# Sheet1.net
KiCad netlist of a schematic drawn in Altium Designer
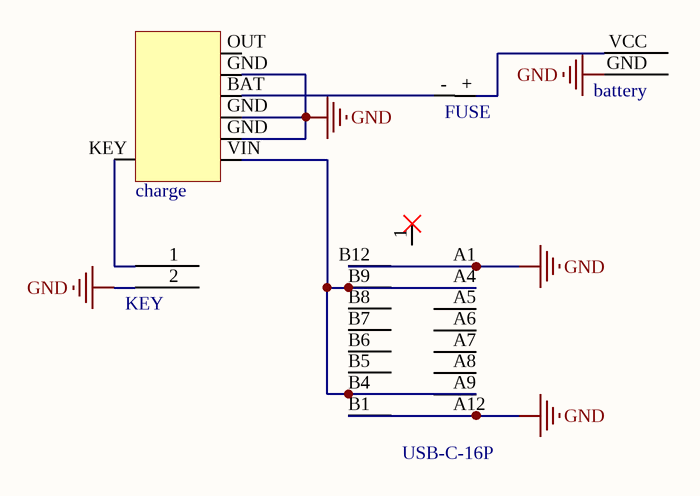
[diagram p0: Sheet1.SchDoc]

(export (version "E")
  (design (tool "Eeschema 10.0.6"))
  (components
    (comp (ref "battery")
      (value "battery")
      (footprint "battery")
      (libsource (lib "Schlib1") (part "battery"))
    )
    (comp (ref "charge") (value "charge") (footprint "charge") (libsource (lib "Schlib1") (part "charge")))
    (comp (ref "FUSE") (value "FUSE") (footprint "fuse") (libsource (lib "Schlib1") (part "FUSE")))
    (comp (ref "KEY") (value "KEY") (footprint "KEY") (libsource (lib "Schlib1") (part "KEY")))
    (comp (ref "USB-C")
      (value "USB-C-16P")
      (footprint "USB-C")
      (libsource (lib "Schlib1") (part "USB-C-16P"))
    )
  )
  (nets
    (net (code "1") (name "GND") (class "Default")
      (node (ref "KEY") (pin "2") (pinfunction "2_2") (pintype "passive"))
      (node (ref "USB-C") (pin "A1") (pinfunction "A1_A1") (pintype "passive"))
      (node (ref "USB-C") (pin "A12") (pinfunction "A12_A12") (pintype "passive"))
      (node (ref "USB-C") (pin "B1") (pinfunction "B1_B1") (pintype "passive"))
      (node (ref "USB-C") (pin "B12") (pinfunction "B12_B12") (pintype "passive"))
      (node (ref "battery") (pin "GND") (pinfunction "GND_GND") (pintype "passive"))
      (node (ref "charge") (pin "GND") (pinfunction "GND_GND") (pintype "passive"))
    )
    (net (code "2") (name "Net-(FUSE-Pad+)") (class "Default")
      (node (ref "FUSE") (pin "+") (pinfunction "+_+") (pintype "passive"))
      (node (ref "battery") (pin "VCC") (pinfunction "VCC_VCC") (pintype "passive"))
    )
    (net (code "3") (name "Net-(FUSE-Pad-)") (class "Default")
      (node (ref "FUSE") (pin "-") (pinfunction "-_-") (pintype "passive"))
      (node (ref "charge") (pin "BAT") (pinfunction "BAT_BAT") (pintype "passive"))
    )
    (net (code "4") (name "Net-(KEY-Pad1)") (class "Default")
      (node (ref "KEY") (pin "1") (pinfunction "1_1") (pintype "passive"))
      (node (ref "charge") (pin "KEY") (pinfunction "KEY_KEY") (pintype "passive"))
    )
    (net (code "5") (name "Net-(USB-C-PadA4)") (class "Default")
      (node (ref "USB-C") (pin "A4") (pinfunction "A4_A4") (pintype "passive"))
      (node (ref "USB-C") (pin "A9") (pinfunction "A9_A9") (pintype "passive"))
      (node (ref "USB-C") (pin "B4") (pinfunction "B4_B4") (pintype "passive"))
      (node (ref "USB-C") (pin "B9") (pinfunction "B9_B9") (pintype "passive"))
      (node (ref "charge") (pin "VIN") (pinfunction "VIN_VIN") (pintype "passive"))
    )
    (net (code "6") (name "unconnected-(USB-C-Pad1)") (class "Default")
      (node (ref "USB-C") (pin "1") (pinfunction "1_1") (pintype "passive+no_connect"))
    )
    (net (code "7") (name "unconnected-(USB-C-PadA5)") (class "Default")
      (node (ref "USB-C") (pin "A5") (pinfunction "A5_A5") (pintype "passive"))
    )
    (net (code "8") (name "unconnected-(USB-C-PadA6)") (class "Default")
      (node (ref "USB-C") (pin "A6") (pinfunction "A6_A6") (pintype "passive"))
    )
    (net (code "9") (name "unconnected-(USB-C-PadA7)") (class "Default")
      (node (ref "USB-C") (pin "A7") (pinfunction "A7_A7") (pintype "passive"))
    )
    (net (code "10") (name "unconnected-(USB-C-PadA8)") (class "Default")
      (node (ref "USB-C") (pin "A8") (pinfunction "A8_A8") (pintype "passive"))
    )
    (net (code "11") (name "unconnected-(USB-C-PadB5)") (class "Default")
      (node (ref "USB-C") (pin "B5") (pinfunction "B5_B5") (pintype "passive"))
    )
    (net (code "12") (name "unconnected-(USB-C-PadB6)") (class "Default")
      (node (ref "USB-C") (pin "B6") (pinfunction "B6_B6") (pintype "passive"))
    )
    (net (code "13") (name "unconnected-(USB-C-PadB7)") (class "Default")
      (node (ref "USB-C") (pin "B7") (pinfunction "B7_B7") (pintype "passive"))
    )
    (net (code "14") (name "unconnected-(USB-C-PadB8)") (class "Default")
      (node (ref "USB-C") (pin "B8") (pinfunction "B8_B8") (pintype "passive"))
    )
    (net (code "15") (name "unconnected-(charge-PadOUT)") (class "Default")
      (node (ref "charge") (pin "OUT") (pinfunction "OUT_OUT") (pintype "passive"))
    )
  )
)
